# L-D5019-01-04.net
KiCad netlist of a schematic drawn in Altium Designer
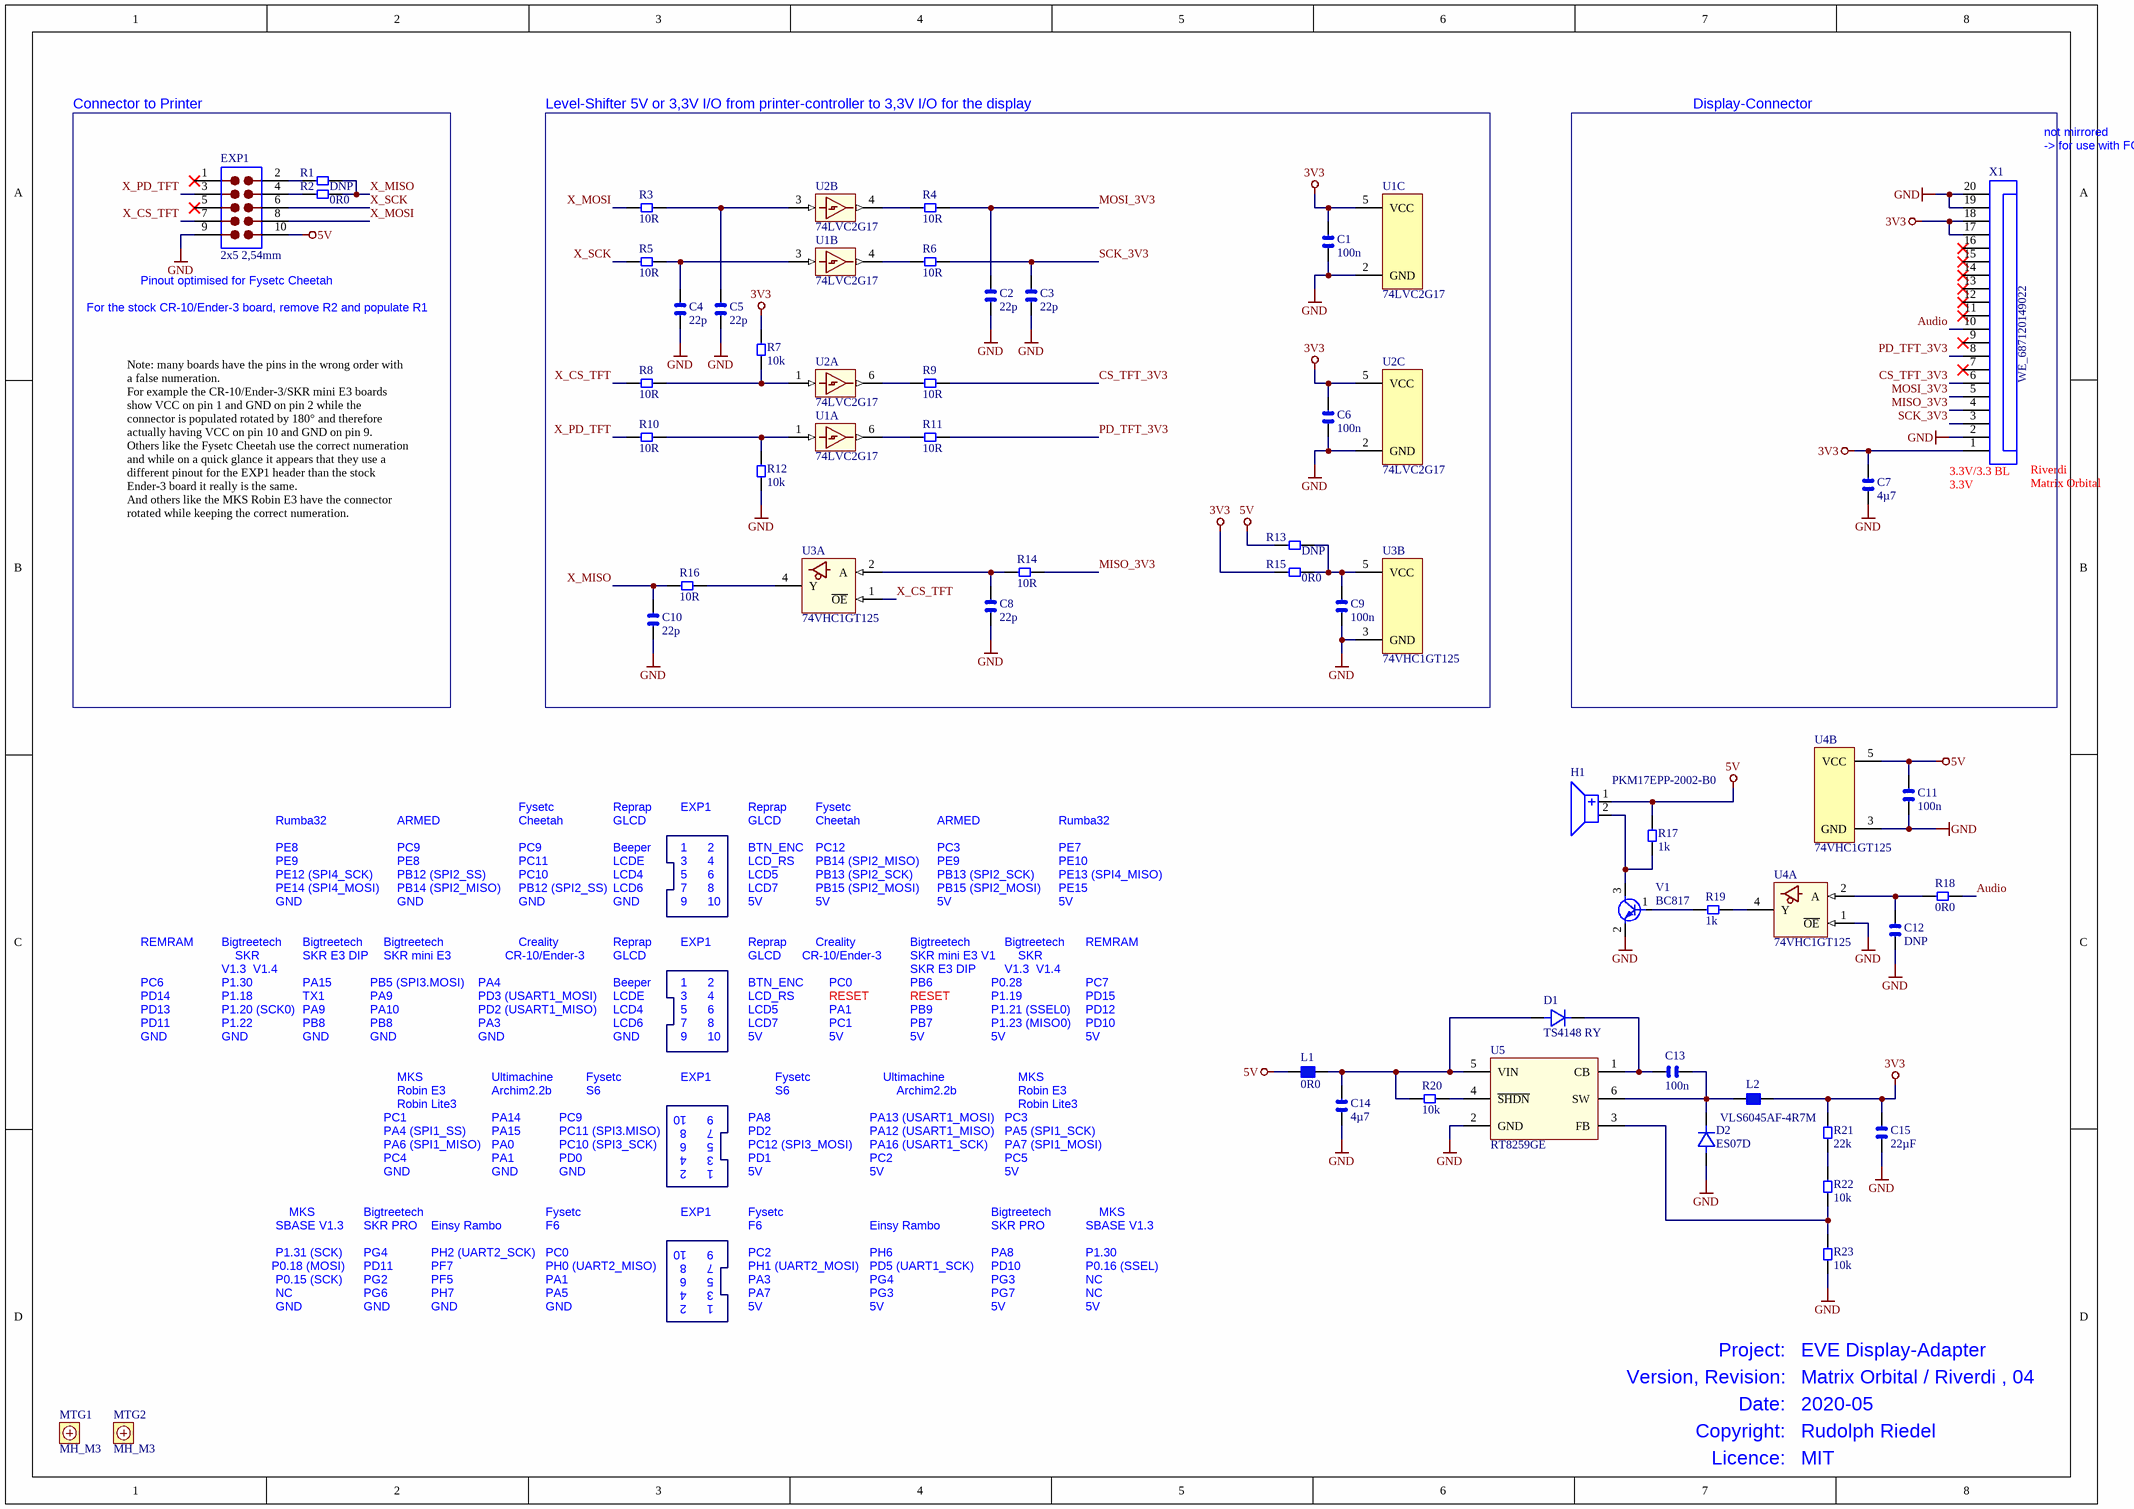
[diagram p0: L-D5019-01-04.SchDoc]

(export (version "E")
  (design (tool "Eeschema 10.0.6"))
  (components
    (comp (ref "C1")
      (value "100n")
      (footprint "CAPC2012X14L")
      (description "0805 Chip Capacitor")
      (fields (field (name "PART NUMBER") "CAPC_0805") (field (name "EDITOR") "rriedel"))
      (libsource (lib "HW-Labor_GF") (part "CAP_2_V2"))
    )
    (comp (ref "C2")
      (value "22p")
      (footprint "CAPC2012X14L")
      (description "0805 Chip Capacitor")
      (fields (field (name "PART NUMBER") "CAPC_0805") (field (name "EDITOR") "rriedel"))
      (libsource (lib "HW-Labor_GF") (part "CAP_2_V2"))
    )
    (comp (ref "C3")
      (value "22p")
      (footprint "CAPC2012X14L")
      (description "0805 Chip Capacitor")
      (fields (field (name "PART NUMBER") "CAPC_0805") (field (name "EDITOR") "rriedel"))
      (libsource (lib "HW-Labor_GF") (part "CAP_2_V2"))
    )
    (comp (ref "C4")
      (value "22p")
      (footprint "CAPC2012X14L")
      (description "0805 Chip Capacitor")
      (fields (field (name "PART NUMBER") "CAPC_0805") (field (name "EDITOR") "rriedel"))
      (libsource (lib "HW-Labor_GF") (part "CAP_2_V2"))
    )
    (comp (ref "C5")
      (value "22p")
      (footprint "CAPC2012X14L")
      (description "0805 Chip Capacitor")
      (fields (field (name "PART NUMBER") "CAPC_0805") (field (name "EDITOR") "rriedel"))
      (libsource (lib "HW-Labor_GF") (part "CAP_2_V2"))
    )
    (comp (ref "C6")
      (value "100n")
      (footprint "CAPC2012X14L")
      (description "0805 Chip Capacitor")
      (fields (field (name "PART NUMBER") "CAPC_0805") (field (name "EDITOR") "rriedel"))
      (libsource (lib "HW-Labor_GF") (part "CAP_2_V2"))
    )
    (comp (ref "C7")
      (value "4µ7")
      (footprint "CAPC2012X14L")
      (description "0805 Chip Capacitor")
      (fields (field (name "PART NUMBER") "CAPC_0805") (field (name "ERSTELLER") "rriedel"))
      (libsource (lib "HW-Labor_GF") (part "CAP_2_V2"))
    )
    (comp (ref "C8")
      (value "22p")
      (footprint "CAPC2012X14L")
      (description "0805 Chip Capacitor")
      (fields (field (name "PART NUMBER") "CAPC_0805") (field (name "EDITOR") "rriedel"))
      (libsource (lib "HW-Labor_GF") (part "CAP_2_V2"))
    )
    (comp (ref "C9")
      (value "100n")
      (footprint "CAPC2012X14L")
      (description "0805 Chip Capacitor")
      (fields (field (name "PART NUMBER") "CAPC_0805") (field (name "EDITOR") "rriedel"))
      (libsource (lib "HW-Labor_GF") (part "CAP_2_V2"))
    )
    (comp (ref "C10")
      (value "22p")
      (footprint "CAPC2012X14L")
      (description "0805 Chip Capacitor")
      (fields (field (name "PART NUMBER") "CAPC_0805") (field (name "EDITOR") "rriedel"))
      (libsource (lib "HW-Labor_GF") (part "CAP_2_V2"))
    )
    (comp (ref "C11")
      (value "100n")
      (footprint "CAPC2012X14L")
      (description "0805 Chip Capacitor")
      (fields (field (name "PART NUMBER") "CAPC_0805") (field (name "EDITOR") "rriedel"))
      (libsource (lib "HW-Labor_GF") (part "CAP_2_V2"))
    )
    (comp (ref "C12")
      (value "DNP")
      (footprint "CAPC2012X14L")
      (description "0805 Chip Capacitor")
      (fields (field (name "PART NUMBER") "CAPC_0805") (field (name "EDITOR") "rriedel"))
      (libsource (lib "HW-Labor_GF") (part "CAP_2_V2"))
    )
    (comp (ref "C13")
      (value "100n")
      (footprint "CAPC2012X14L")
      (description "0805 Chip Capacitor")
      (fields (field (name "PART NUMBER") "CAPC_0805") (field (name "EDITOR") "rriedel"))
      (libsource (lib "HW-Labor_GF") (part "CAP_2_V2"))
    )
    (comp (ref "C14")
      (value "4µ7")
      (footprint "CAPC2012X14L")
      (description "0805 Chip Capacitor")
      (fields (field (name "PART NUMBER") "CAPC_0805") (field (name "ERSTELLER") "rriedel"))
      (libsource (lib "HW-Labor_GF") (part "CAP_2_V2"))
    )
    (comp (ref "C15")
      (value "22µF")
      (footprint "CAPC3216X19N")
      (description "1206 Chip Capacitor")
      (fields (field (name "PART NUMBER") "CAPC_1206") (field (name "EDITOR") "rriedel"))
      (libsource (lib "HW-Labor_GF") (part "CAP_2_V2"))
    )
    (comp (ref "D1")
      (value "TS4148 RY")
      (footprint "DIOC2012X10N")
      (description "Small Signal Diode IF 0.3A, VR 75V, 0805")
      (fields
        (field (name "PART NUMBER") "TSC_TS4148 RY")
        (field (name "MANUFACTURER") "TSC")
        (field (name "EDITOR") "rriedel")
      )
      (libsource (lib "HW-Labor_GF") (part "Diode_A2_K1"))
    )
    (comp (ref "D2")
      (value "ES07D")
      (footprint "DIOM2818X11N")
      (description "Ultrafast Rectifier Surface Mount,  IF 0.5A, VR 100V, DO-219AB, AEC-Q101")
      (fields (field (name "MANUFACTURER") "Vishay") (field (name "EDITOR") "rriedel"))
      (libsource (lib "HW-Labor_GF") (part "Diode_A2_K1"))
    )
    (comp (ref "EXP1")
      (value "2x5 2,54mm")
      (footprint "PINH_2x5_2_54mm_shroud")
      (description "Pin-Header 2,54 mm 2x5pins, shrouded")
      (fields (field (name "PART NUMBER") "PINH_2x5_2_54") (field (name "EDITOR") "rriedel"))
      (libsource (lib "HW-Labor_GF") (part "CONM_2x5_V2"))
    )
    (comp (ref "H1")
      (value "PKM17EPP-2002-B0")
      (footprint "Speaker_17mm")
      (description "Speaker, Piezo, THT, dia 17mm,  height 8.6 mm")
      (fields
        (field (name "MANUFACTURER") "Murata")
        (field (name "DISTRIBUTOR_1_PART_NUMBER") "490-4688-ND")
        (field (name "EDITOR") "rriedel")
      )
      (libsource (lib "HW-Labor_GF") (part "Speaker"))
    )
    (comp (ref "L1")
      (value "0R0")
      (footprint "INDC2012X10L")
      (description "0805 Chip Inductor")
      (fields (field (name "PART NUMBER") "INDC_0805") (field (name "EDITOR") "rriedel"))
      (libsource (lib "HW-Labor_GF") (part "IND_2_V1"))
    )
    (comp (ref "L2")
      (value "VLS6045AF-4R7M")
      (footprint "PowerInductor_6x6")
      (description "4,7µH, shielded, 4,7A, 26mR")
      (fields
        (field (name "MANUFACTURER") "TDK")
        (field (name "DISTRIBUTOR_1_PART_NUMBER") "445-180835-1-ND")
        (field (name "EDITOR") "rriedel")
      )
      (libsource (lib "HW-Labor_GF") (part "IND_2_V1"))
    )
    (comp (ref "MTG1")
      (value "MH_M3")
      (footprint "HOLE_3_2MM")
      (description "Mounting-Hole for M3 screws")
      (fields (field (name "EDITOR") "rriedel"))
      (libsource (lib "HW-Labor_GF") (part "MTG_V1"))
    )
    (comp (ref "MTG2")
      (value "MH_M3")
      (footprint "HOLE_3_2MM")
      (description "Mounting-Hole for M3 screws")
      (fields (field (name "EDITOR") "rriedel"))
      (libsource (lib "HW-Labor_GF") (part "MTG_V1"))
    )
    (comp (ref "R1")
      (value "DNP")
      (footprint "RESC2012X06L")
      (description "0805 Chip Resistor")
      (fields (field (name "PART NUMBER") "RESC_0805") (field (name "EDITOR") "rriedel"))
      (libsource (lib "HW-Labor_GF") (part "RES_2_V2"))
    )
    (comp (ref "R2")
      (value "0R0")
      (footprint "RESC2012X06L")
      (description "0805 Chip Resistor")
      (fields (field (name "PART NUMBER") "RESC_0805") (field (name "EDITOR") "rriedel"))
      (libsource (lib "HW-Labor_GF") (part "RES_2_V2"))
    )
    (comp (ref "R3")
      (value "10R")
      (footprint "RESC2012X06L")
      (description "0805 Chip Resistor")
      (fields (field (name "PART NUMBER") "RESC_0805") (field (name "EDITOR") "rriedel"))
      (libsource (lib "HW-Labor_GF") (part "RES_2_V2"))
    )
    (comp (ref "R4")
      (value "10R")
      (footprint "RESC2012X06L")
      (description "0805 Chip Resistor")
      (fields (field (name "PART NUMBER") "RESC_0805") (field (name "EDITOR") "rriedel"))
      (libsource (lib "HW-Labor_GF") (part "RES_2_V2"))
    )
    (comp (ref "R5")
      (value "10R")
      (footprint "RESC2012X06L")
      (description "0805 Chip Resistor")
      (fields (field (name "PART NUMBER") "RESC_0805") (field (name "EDITOR") "rriedel"))
      (libsource (lib "HW-Labor_GF") (part "RES_2_V2"))
    )
    (comp (ref "R6")
      (value "10R")
      (footprint "RESC2012X06L")
      (description "0805 Chip Resistor")
      (fields (field (name "PART NUMBER") "RESC_0805") (field (name "EDITOR") "rriedel"))
      (libsource (lib "HW-Labor_GF") (part "RES_2_V2"))
    )
    (comp (ref "R7")
      (value "10k")
      (footprint "RESC2012X06L")
      (description "0805 Chip Resistor")
      (fields (field (name "PART NUMBER") "RESC_0805") (field (name "EDITOR") "rriedel"))
      (libsource (lib "HW-Labor_GF") (part "RES_2_V2"))
    )
    (comp (ref "R8")
      (value "10R")
      (footprint "RESC2012X06L")
      (description "0805 Chip Resistor")
      (fields (field (name "PART NUMBER") "RESC_0805") (field (name "EDITOR") "rriedel"))
      (libsource (lib "HW-Labor_GF") (part "RES_2_V2"))
    )
    (comp (ref "R9")
      (value "10R")
      (footprint "RESC2012X06L")
      (description "0805 Chip Resistor")
      (fields (field (name "PART NUMBER") "RESC_0805") (field (name "EDITOR") "rriedel"))
      (libsource (lib "HW-Labor_GF") (part "RES_2_V2"))
    )
    (comp (ref "R10")
      (value "10R")
      (footprint "RESC2012X06L")
      (description "0805 Chip Resistor")
      (fields (field (name "PART NUMBER") "RESC_0805") (field (name "EDITOR") "rriedel"))
      (libsource (lib "HW-Labor_GF") (part "RES_2_V2"))
    )
    (comp (ref "R11")
      (value "10R")
      (footprint "RESC2012X06L")
      (description "0805 Chip Resistor")
      (fields (field (name "PART NUMBER") "RESC_0805") (field (name "EDITOR") "rriedel"))
      (libsource (lib "HW-Labor_GF") (part "RES_2_V2"))
    )
    (comp (ref "R12")
      (value "10k")
      (footprint "RESC2012X06L")
      (description "0805 Chip Resistor")
      (fields (field (name "PART NUMBER") "RESC_0805") (field (name "EDITOR") "rriedel"))
      (libsource (lib "HW-Labor_GF") (part "RES_2_V2"))
    )
    (comp (ref "R13")
      (value "DNP")
      (footprint "RESC2012X06L")
      (description "0805 Chip Resistor")
      (fields (field (name "PART NUMBER") "RESC_0805") (field (name "EDITOR") "rriedel"))
      (libsource (lib "HW-Labor_GF") (part "RES_2_V2"))
    )
    (comp (ref "R14")
      (value "10R")
      (footprint "RESC2012X06L")
      (description "0805 Chip Resistor")
      (fields (field (name "PART NUMBER") "RESC_0805") (field (name "EDITOR") "rriedel"))
      (libsource (lib "HW-Labor_GF") (part "RES_2_V2"))
    )
    (comp (ref "R15")
      (value "0R0")
      (footprint "RESC2012X06L")
      (description "0805 Chip Resistor")
      (fields (field (name "PART NUMBER") "RESC_0805") (field (name "EDITOR") "rriedel"))
      (libsource (lib "HW-Labor_GF") (part "RES_2_V2"))
    )
    (comp (ref "R16")
      (value "10R")
      (footprint "RESC2012X06L")
      (description "0805 Chip Resistor")
      (fields (field (name "PART NUMBER") "RESC_0805") (field (name "EDITOR") "rriedel"))
      (libsource (lib "HW-Labor_GF") (part "RES_2_V2"))
    )
    (comp (ref "R17")
      (value "1k")
      (footprint "RESC2012X06L")
      (description "0805 Chip Resistor")
      (fields (field (name "PART NUMBER") "RESC_0805") (field (name "EDITOR") "rriedel"))
      (libsource (lib "HW-Labor_GF") (part "RES_2_V2"))
    )
    (comp (ref "R18")
      (value "0R0")
      (footprint "RESC2012X06L")
      (description "0805 Chip Resistor")
      (fields (field (name "PART NUMBER") "RESC_0805") (field (name "EDITOR") "rriedel"))
      (libsource (lib "HW-Labor_GF") (part "RES_2_V2"))
    )
    (comp (ref "R19")
      (value "1k")
      (footprint "RESC2012X06L")
      (description "0805 Chip Resistor")
      (fields (field (name "PART NUMBER") "RESC_0805") (field (name "EDITOR") "rriedel"))
      (libsource (lib "HW-Labor_GF") (part "RES_2_V2"))
    )
    (comp (ref "R20")
      (value "10k")
      (footprint "RESC2012X06L")
      (description "0805 Chip Resistor")
      (fields (field (name "PART NUMBER") "RESC_0805") (field (name "EDITOR") "rriedel"))
      (libsource (lib "HW-Labor_GF") (part "RES_2_V2"))
    )
    (comp (ref "R21")
      (value "22k")
      (footprint "RESC2012X06L")
      (description "0805 Chip Resistor")
      (fields (field (name "PART NUMBER") "RESC_0805") (field (name "EDITOR") "rriedel"))
      (libsource (lib "HW-Labor_GF") (part "RES_2_V2"))
    )
    (comp (ref "R22")
      (value "10k")
      (footprint "RESC2012X06L")
      (description "0805 Chip Resistor")
      (fields (field (name "PART NUMBER") "RESC_0805") (field (name "EDITOR") "rriedel"))
      (libsource (lib "HW-Labor_GF") (part "RES_2_V2"))
    )
    (comp (ref "R23")
      (value "10k")
      (footprint "RESC2012X06L")
      (description "0805 Chip Resistor")
      (fields (field (name "PART NUMBER") "RESC_0805") (field (name "EDITOR") "rriedel"))
      (libsource (lib "HW-Labor_GF") (part "RES_2_V2"))
    )
    (comp (ref "U1")
      (value "74LVC2G17")
      (footprint "SOT95P280X110-6N")
      (description "Dual Schmitt-Trigger Buffer with 5.5V tolerant inputs")
      (fields
        (field (name "MANUFACTURER") "TI")
        (field (name "DISTRIBUTOR_1_PART_NUMBER") "296-SN74LVC2G17DBVRCT-ND‎")
        (field (name "EDITOR") "rriedel")
      )
      (libsource (lib "HW-Labor_GF") (part "74LVC2G17"))
    )
    (comp (ref "U2")
      (value "74LVC2G17")
      (footprint "SOT95P280X110-6N")
      (description "Dual Schmitt-Trigger Buffer with 5.5V tolerant inputs")
      (fields
        (field (name "MANUFACTURER") "TI")
        (field (name "DISTRIBUTOR_1_PART_NUMBER") "296-SN74LVC2G17DBVRCT-ND‎")
        (field (name "EDITOR") "rriedel")
      )
      (libsource (lib "HW-Labor_GF") (part "74LVC2G17"))
    )
    (comp (ref "U3")
      (value "74VHC1GT125")
      (footprint "SOT95P280X110-5N")
      (description "1x Buffer with OE; 3-state,Level Shifter 3,3V to 5V and 5V to 3.3V")
      (fields
        (field (name "MANUFACTURER") "ON Semiconductor")
        (field (name "DISTRIBUTOR_1_PART_NUMBER") "1703291")
        (field (name "EDITOR") "rriedel")
      )
      (libsource (lib "HW-Labor_GF") (part "74LVC1G125G"))
    )
    (comp (ref "U4")
      (value "74VHC1GT125")
      (footprint "SOT95P280X110-5N")
      (description "1x Buffer with OE; 3-state,Level Shifter 3,3V to 5V and 5V to 3.3V")
      (fields
        (field (name "MANUFACTURER") "ON Semiconductor")
        (field (name "DISTRIBUTOR_1_PART_NUMBER") "1703291")
        (field (name "EDITOR") "rriedel")
      )
      (libsource (lib "") (part "74LVC1G125G_1"))
    )
    (comp (ref "U5")
      (value "RT8259GE")
      (footprint "SOT95P280X110-6N")
      (description "Step-Down DC/DC Regulator, 24V, 1.2A, 1,4MHz")
      (fields
        (field (name "MANUFACTURER") "Richtek")
        (field (name "DISTRIBUTOR_1_PART_NUMBER") "1028-1497-1-ND")
        (field (name "EDITOR") "rriedel")
      )
      (libsource (lib "HW-Labor_GF") (part "StepDown_SOT23-6"))
    )
    (comp (ref "V1")
      (value "BC817")
      (footprint "SOT95P280X110-3N")
      (description "NPN Transistor SOT23, 1=B, 2=C, 3=E")
      (fields (field (name "EDITOR") "rriedel"))
      (libsource (lib "HW-Labor_GF") (part "NPN_B1_C2_E3"))
    )
    (comp (ref "X1")
      (value "WE_687120149022")
      (footprint "WE_687120149022")
      (description "20pin WR-FPC 0.50 mm SMT ZIF Horizontal - Bottom Contact")
      (fields
        (field (name "MANUFACTURER") "Wuerth")
        (field (name "DISTRIBUTOR_1_PART_NUMBER") "732-6002-1-ND")
        (field (name "EDITOR") "rriedel")
      )
      (libsource (lib "HW-Labor_GF") (part "FPC_20"))
    )
  )
  (nets
    (net (code "1") (name "/Audio") (class "Default")
      (node (ref "R18") (pin "2") (pinfunction "2_2") (pintype "passive"))
      (node (ref "X1") (pin "10") (pinfunction "10_10") (pintype "passive"))
    )
    (net (code "2") (name "/CS_TFT_3V3") (class "Default")
      (node (ref "R9") (pin "2") (pinfunction "2_2") (pintype "passive"))
      (node (ref "X1") (pin "6") (pinfunction "6_6") (pintype "passive"))
    )
    (net (code "3") (name "/MISO_3V3") (class "Default")
      (node (ref "R14") (pin "2") (pinfunction "2_2") (pintype "passive"))
      (node (ref "X1") (pin "4") (pinfunction "4_4") (pintype "passive"))
    )
    (net (code "4") (name "/MOSI_3V3") (class "Default")
      (node (ref "C2") (pin "2") (pinfunction "2_2") (pintype "passive"))
      (node (ref "R4") (pin "2") (pinfunction "2_2") (pintype "passive"))
      (node (ref "X1") (pin "5") (pinfunction "5_5") (pintype "passive"))
    )
    (net (code "5") (name "/PD_TFT_3V3") (class "Default")
      (node (ref "R11") (pin "2") (pinfunction "2_2") (pintype "passive"))
      (node (ref "X1") (pin "8") (pinfunction "8_8") (pintype "passive"))
    )
    (net (code "6") (name "/SCK_3V3") (class "Default")
      (node (ref "C3") (pin "2") (pinfunction "2_2") (pintype "passive"))
      (node (ref "R6") (pin "2") (pinfunction "2_2") (pintype "passive"))
      (node (ref "X1") (pin "3") (pinfunction "3_3") (pintype "passive"))
    )
    (net (code "7") (name "/X_CS_TFT") (class "Default")
      (node (ref "EXP1") (pin "7") (pinfunction "7_7") (pintype "passive"))
      (node (ref "R8") (pin "1") (pinfunction "1_1") (pintype "passive"))
      (node (ref "U3") (pin "1") (pinfunction "~{OE}_1") (pintype "input"))
    )
    (net (code "8") (name "/X_MISO") (class "Default")
      (node (ref "C10") (pin "2") (pinfunction "2_2") (pintype "passive"))
      (node (ref "R1") (pin "2") (pinfunction "2_2") (pintype "passive"))
      (node (ref "R16") (pin "1") (pinfunction "1_1") (pintype "passive"))
      (node (ref "R2") (pin "2") (pinfunction "2_2") (pintype "passive"))
    )
    (net (code "9") (name "/X_MOSI") (class "Default")
      (node (ref "EXP1") (pin "8") (pinfunction "8_8") (pintype "passive"))
      (node (ref "R3") (pin "1") (pinfunction "1_1") (pintype "passive"))
    )
    (net (code "10") (name "/X_PD_TFT") (class "Default")
      (node (ref "EXP1") (pin "3") (pinfunction "3_3") (pintype "passive"))
      (node (ref "R10") (pin "1") (pinfunction "1_1") (pintype "passive"))
    )
    (net (code "11") (name "/X_SCK") (class "Default")
      (node (ref "EXP1") (pin "6") (pinfunction "6_6") (pintype "passive"))
      (node (ref "R5") (pin "1") (pinfunction "1_1") (pintype "passive"))
    )
    (net (code "12") (name "3V3") (class "Default")
      (node (ref "C1") (pin "2") (pinfunction "2_2") (pintype "passive"))
      (node (ref "C15") (pin "2") (pinfunction "2_2") (pintype "passive"))
      (node (ref "C6") (pin "2") (pinfunction "2_2") (pintype "passive"))
      (node (ref "C7") (pin "2") (pinfunction "2_2") (pintype "passive"))
      (node (ref "L2") (pin "2") (pinfunction "2_2") (pintype "passive"))
      (node (ref "R15") (pin "1") (pinfunction "1_1") (pintype "passive"))
      (node (ref "R21") (pin "2") (pinfunction "2_2") (pintype "passive"))
      (node (ref "R7") (pin "2") (pinfunction "2_2") (pintype "passive"))
      (node (ref "U1") (pin "5") (pinfunction "VCC_5") (pintype "power_in"))
      (node (ref "U2") (pin "5") (pinfunction "VCC_5") (pintype "power_in"))
      (node (ref "X1") (pin "1") (pinfunction "1_1") (pintype "passive"))
      (node (ref "X1") (pin "17") (pinfunction "17_17") (pintype "passive"))
      (node (ref "X1") (pin "18") (pinfunction "18_18") (pintype "passive"))
    )
    (net (code "13") (name "5V") (class "Default")
      (node (ref "C11") (pin "2") (pinfunction "2_2") (pintype "passive"))
      (node (ref "EXP1") (pin "10") (pinfunction "10_10") (pintype "passive"))
      (node (ref "H1") (pin "1") (pinfunction "1_1") (pintype "passive"))
      (node (ref "L1") (pin "1") (pinfunction "1_1") (pintype "passive"))
      (node (ref "R13") (pin "1") (pinfunction "1_1") (pintype "passive"))
      (node (ref "R17") (pin "2") (pinfunction "2_2") (pintype "passive"))
      (node (ref "U4") (pin "5") (pinfunction "VCC_5") (pintype "passive"))
    )
    (net (code "14") (name "GND") (class "Default")
      (node (ref "C1") (pin "1") (pinfunction "1_1") (pintype "passive"))
      (node (ref "C10") (pin "1") (pinfunction "1_1") (pintype "passive"))
      (node (ref "C11") (pin "1") (pinfunction "1_1") (pintype "passive"))
      (node (ref "C12") (pin "1") (pinfunction "1_1") (pintype "passive"))
      (node (ref "C14") (pin "1") (pinfunction "1_1") (pintype "passive"))
      (node (ref "C15") (pin "1") (pinfunction "1_1") (pintype "passive"))
      (node (ref "C2") (pin "1") (pinfunction "1_1") (pintype "passive"))
      (node (ref "C3") (pin "1") (pinfunction "1_1") (pintype "passive"))
      (node (ref "C4") (pin "1") (pinfunction "1_1") (pintype "passive"))
      (node (ref "C5") (pin "1") (pinfunction "1_1") (pintype "passive"))
      (node (ref "C6") (pin "1") (pinfunction "1_1") (pintype "passive"))
      (node (ref "C7") (pin "1") (pinfunction "1_1") (pintype "passive"))
      (node (ref "C8") (pin "1") (pinfunction "1_1") (pintype "passive"))
      (node (ref "C9") (pin "1") (pinfunction "1_1") (pintype "passive"))
      (node (ref "D2") (pin "2") (pinfunction "2_2") (pintype "passive"))
      (node (ref "EXP1") (pin "9") (pinfunction "9_9") (pintype "passive"))
      (node (ref "R12") (pin "1") (pinfunction "1_1") (pintype "passive"))
      (node (ref "R23") (pin "1") (pinfunction "1_1") (pintype "passive"))
      (node (ref "U1") (pin "2") (pinfunction "GND_2") (pintype "power_in"))
      (node (ref "U2") (pin "2") (pinfunction "GND_2") (pintype "power_in"))
      (node (ref "U3") (pin "3") (pinfunction "GND_3") (pintype "passive"))
      (node (ref "U4") (pin "1") (pinfunction "~{OE}_1") (pintype "input"))
      (node (ref "U4") (pin "3") (pinfunction "GND_3") (pintype "passive"))
      (node (ref "U5") (pin "2") (pinfunction "GND_2") (pintype "power_in"))
      (node (ref "V1") (pin "2") (pinfunction "2_2") (pintype "passive"))
      (node (ref "X1") (pin "19") (pinfunction "19_19") (pintype "passive"))
      (node (ref "X1") (pin "2") (pinfunction "2_2") (pintype "passive"))
      (node (ref "X1") (pin "20") (pinfunction "20_20") (pintype "passive"))
    )
    (net (code "15") (name "Net-(EXP1-Pad2)") (class "Default")
      (node (ref "EXP1") (pin "2") (pinfunction "2_2") (pintype "passive"))
      (node (ref "R1") (pin "1") (pinfunction "1_1") (pintype "passive"))
    )
    (net (code "16") (name "Net-(EXP1-Pad4)") (class "Default")
      (node (ref "EXP1") (pin "4") (pinfunction "4_4") (pintype "passive"))
      (node (ref "R2") (pin "1") (pinfunction "1_1") (pintype "passive"))
    )
    (net (code "17") (name "Net-(H1-Pad2)") (class "Default")
      (node (ref "H1") (pin "2") (pinfunction "2_2") (pintype "passive"))
      (node (ref "R17") (pin "1") (pinfunction "1_1") (pintype "passive"))
      (node (ref "V1") (pin "3") (pinfunction "3_3") (pintype "passive"))
    )
    (net (code "18") (name "Net-(R19-Pad2)") (class "Default")
      (node (ref "R19") (pin "2") (pinfunction "2_2") (pintype "passive"))
      (node (ref "V1") (pin "1") (pinfunction "1_1") (pintype "passive"))
    )
    (net (code "19") (name "Net-(R21-Pad1)") (class "Default")
      (node (ref "R21") (pin "1") (pinfunction "1_1") (pintype "passive"))
      (node (ref "R22") (pin "2") (pinfunction "2_2") (pintype "passive"))
    )
    (net (code "20") (name "Net-(U1A-1A)") (class "Default")
      (node (ref "R10") (pin "2") (pinfunction "2_2") (pintype "passive"))
      (node (ref "R12") (pin "2") (pinfunction "2_2") (pintype "passive"))
      (node (ref "U1") (pin "1") (pinfunction "1A_1") (pintype "input"))
    )
    (net (code "21") (name "Net-(U1A-1Y)") (class "Default")
      (node (ref "R11") (pin "1") (pinfunction "1_1") (pintype "passive"))
      (node (ref "U1") (pin "6") (pinfunction "1Y_6") (pintype "output"))
    )
    (net (code "22") (name "Net-(U1B-2A)") (class "Default")
      (node (ref "C4") (pin "2") (pinfunction "2_2") (pintype "passive"))
      (node (ref "R5") (pin "2") (pinfunction "2_2") (pintype "passive"))
      (node (ref "U1") (pin "3") (pinfunction "2A_3") (pintype "input"))
    )
    (net (code "23") (name "Net-(U1B-2Y)") (class "Default")
      (node (ref "R6") (pin "1") (pinfunction "1_1") (pintype "passive"))
      (node (ref "U1") (pin "4") (pinfunction "2Y_4") (pintype "output"))
    )
    (net (code "24") (name "Net-(U2A-1A)") (class "Default")
      (node (ref "R7") (pin "1") (pinfunction "1_1") (pintype "passive"))
      (node (ref "R8") (pin "2") (pinfunction "2_2") (pintype "passive"))
      (node (ref "U2") (pin "1") (pinfunction "1A_1") (pintype "input"))
    )
    (net (code "25") (name "Net-(U2A-1Y)") (class "Default")
      (node (ref "R9") (pin "1") (pinfunction "1_1") (pintype "passive"))
      (node (ref "U2") (pin "6") (pinfunction "1Y_6") (pintype "output"))
    )
    (net (code "26") (name "Net-(U2B-2A)") (class "Default")
      (node (ref "C5") (pin "2") (pinfunction "2_2") (pintype "passive"))
      (node (ref "R3") (pin "2") (pinfunction "2_2") (pintype "passive"))
      (node (ref "U2") (pin "3") (pinfunction "2A_3") (pintype "input"))
    )
    (net (code "27") (name "Net-(U2B-2Y)") (class "Default")
      (node (ref "R4") (pin "1") (pinfunction "1_1") (pintype "passive"))
      (node (ref "U2") (pin "4") (pinfunction "2Y_4") (pintype "output"))
    )
    (net (code "28") (name "Net-(U3A-A)") (class "Default")
      (node (ref "C8") (pin "2") (pinfunction "2_2") (pintype "passive"))
      (node (ref "R14") (pin "1") (pinfunction "1_1") (pintype "passive"))
      (node (ref "U3") (pin "2") (pinfunction "A_2") (pintype "input"))
    )
    (net (code "29") (name "Net-(U3A-Y)") (class "Default")
      (node (ref "R16") (pin "2") (pinfunction "2_2") (pintype "passive"))
      (node (ref "U3") (pin "4") (pinfunction "Y_4") (pintype "tri_state"))
    )
    (net (code "30") (name "Net-(U3B-VCC)") (class "Default")
      (node (ref "C9") (pin "2") (pinfunction "2_2") (pintype "passive"))
      (node (ref "R13") (pin "2") (pinfunction "2_2") (pintype "passive"))
      (node (ref "R15") (pin "2") (pinfunction "2_2") (pintype "passive"))
      (node (ref "U3") (pin "5") (pinfunction "VCC_5") (pintype "passive"))
    )
    (net (code "31") (name "Net-(U4A-A)") (class "Default")
      (node (ref "C12") (pin "2") (pinfunction "2_2") (pintype "passive"))
      (node (ref "R18") (pin "1") (pinfunction "1_1") (pintype "passive"))
      (node (ref "U4") (pin "2") (pinfunction "A_2") (pintype "input"))
    )
    (net (code "32") (name "Net-(U4A-Y)") (class "Default")
      (node (ref "R19") (pin "1") (pinfunction "1_1") (pintype "passive"))
      (node (ref "U4") (pin "4") (pinfunction "Y_4") (pintype "tri_state"))
    )
    (net (code "33") (name "Net-(U5-CB)") (class "Default")
      (node (ref "C13") (pin "1") (pinfunction "1_1") (pintype "passive"))
      (node (ref "D1") (pin "1") (pinfunction "1_1") (pintype "passive"))
      (node (ref "U5") (pin "1") (pinfunction "CB_1") (pintype "passive"))
    )
    (net (code "34") (name "Net-(U5-FB)") (class "Default")
      (node (ref "R22") (pin "1") (pinfunction "1_1") (pintype "passive"))
      (node (ref "R23") (pin "2") (pinfunction "2_2") (pintype "passive"))
      (node (ref "U5") (pin "3") (pinfunction "FB_3") (pintype "passive"))
    )
    (net (code "35") (name "Net-(U5-SW)") (class "Default")
      (node (ref "C13") (pin "2") (pinfunction "2_2") (pintype "passive"))
      (node (ref "D2") (pin "1") (pinfunction "1_1") (pintype "passive"))
      (node (ref "L2") (pin "1") (pinfunction "1_1") (pintype "passive"))
      (node (ref "U5") (pin "6") (pinfunction "SW_6") (pintype "passive"))
    )
    (net (code "36") (name "Net-(U5-VIN)") (class "Default")
      (node (ref "C14") (pin "2") (pinfunction "2_2") (pintype "passive"))
      (node (ref "D1") (pin "2") (pinfunction "2_2") (pintype "passive"))
      (node (ref "L1") (pin "2") (pinfunction "2_2") (pintype "passive"))
      (node (ref "R20") (pin "1") (pinfunction "1_1") (pintype "passive"))
      (node (ref "U5") (pin "5") (pinfunction "VIN_5") (pintype "power_in"))
    )
    (net (code "37") (name "Net-(U5-~{SHDN})") (class "Default")
      (node (ref "R20") (pin "2") (pinfunction "2_2") (pintype "passive"))
      (node (ref "U5") (pin "4") (pinfunction "~{SHDN}_4") (pintype "passive"))
    )
    (net (code "38") (name "unconnected-(EXP1-Pad1)") (class "Default")
      (node (ref "EXP1") (pin "1") (pinfunction "1_1") (pintype "passive+no_connect"))
    )
    (net (code "39") (name "unconnected-(EXP1-Pad5)") (class "Default")
      (node (ref "EXP1") (pin "5") (pinfunction "5_5") (pintype "passive+no_connect"))
    )
    (net (code "40") (name "unconnected-(X1-Pad7)") (class "Default")
      (node (ref "X1") (pin "7") (pinfunction "7_7") (pintype "passive+no_connect"))
    )
    (net (code "41") (name "unconnected-(X1-Pad9)") (class "Default")
      (node (ref "X1") (pin "9") (pinfunction "9_9") (pintype "passive+no_connect"))
    )
    (net (code "42") (name "unconnected-(X1-Pad11)") (class "Default")
      (node (ref "X1") (pin "11") (pinfunction "11_11") (pintype "passive+no_connect"))
    )
    (net (code "43") (name "unconnected-(X1-Pad12)") (class "Default")
      (node (ref "X1") (pin "12") (pinfunction "12_12") (pintype "passive+no_connect"))
    )
    (net (code "44") (name "unconnected-(X1-Pad13)") (class "Default")
      (node (ref "X1") (pin "13") (pinfunction "13_13") (pintype "passive+no_connect"))
    )
    (net (code "45") (name "unconnected-(X1-Pad14)") (class "Default")
      (node (ref "X1") (pin "14") (pinfunction "14_14") (pintype "passive+no_connect"))
    )
    (net (code "46") (name "unconnected-(X1-Pad15)") (class "Default")
      (node (ref "X1") (pin "15") (pinfunction "15_15") (pintype "passive+no_connect"))
    )
    (net (code "47") (name "unconnected-(X1-Pad16)") (class "Default")
      (node (ref "X1") (pin "16") (pinfunction "16_16") (pintype "passive+no_connect"))
    )
  )
)
